# Peripherals.net
KiCad netlist of a schematic drawn in Altium Designer
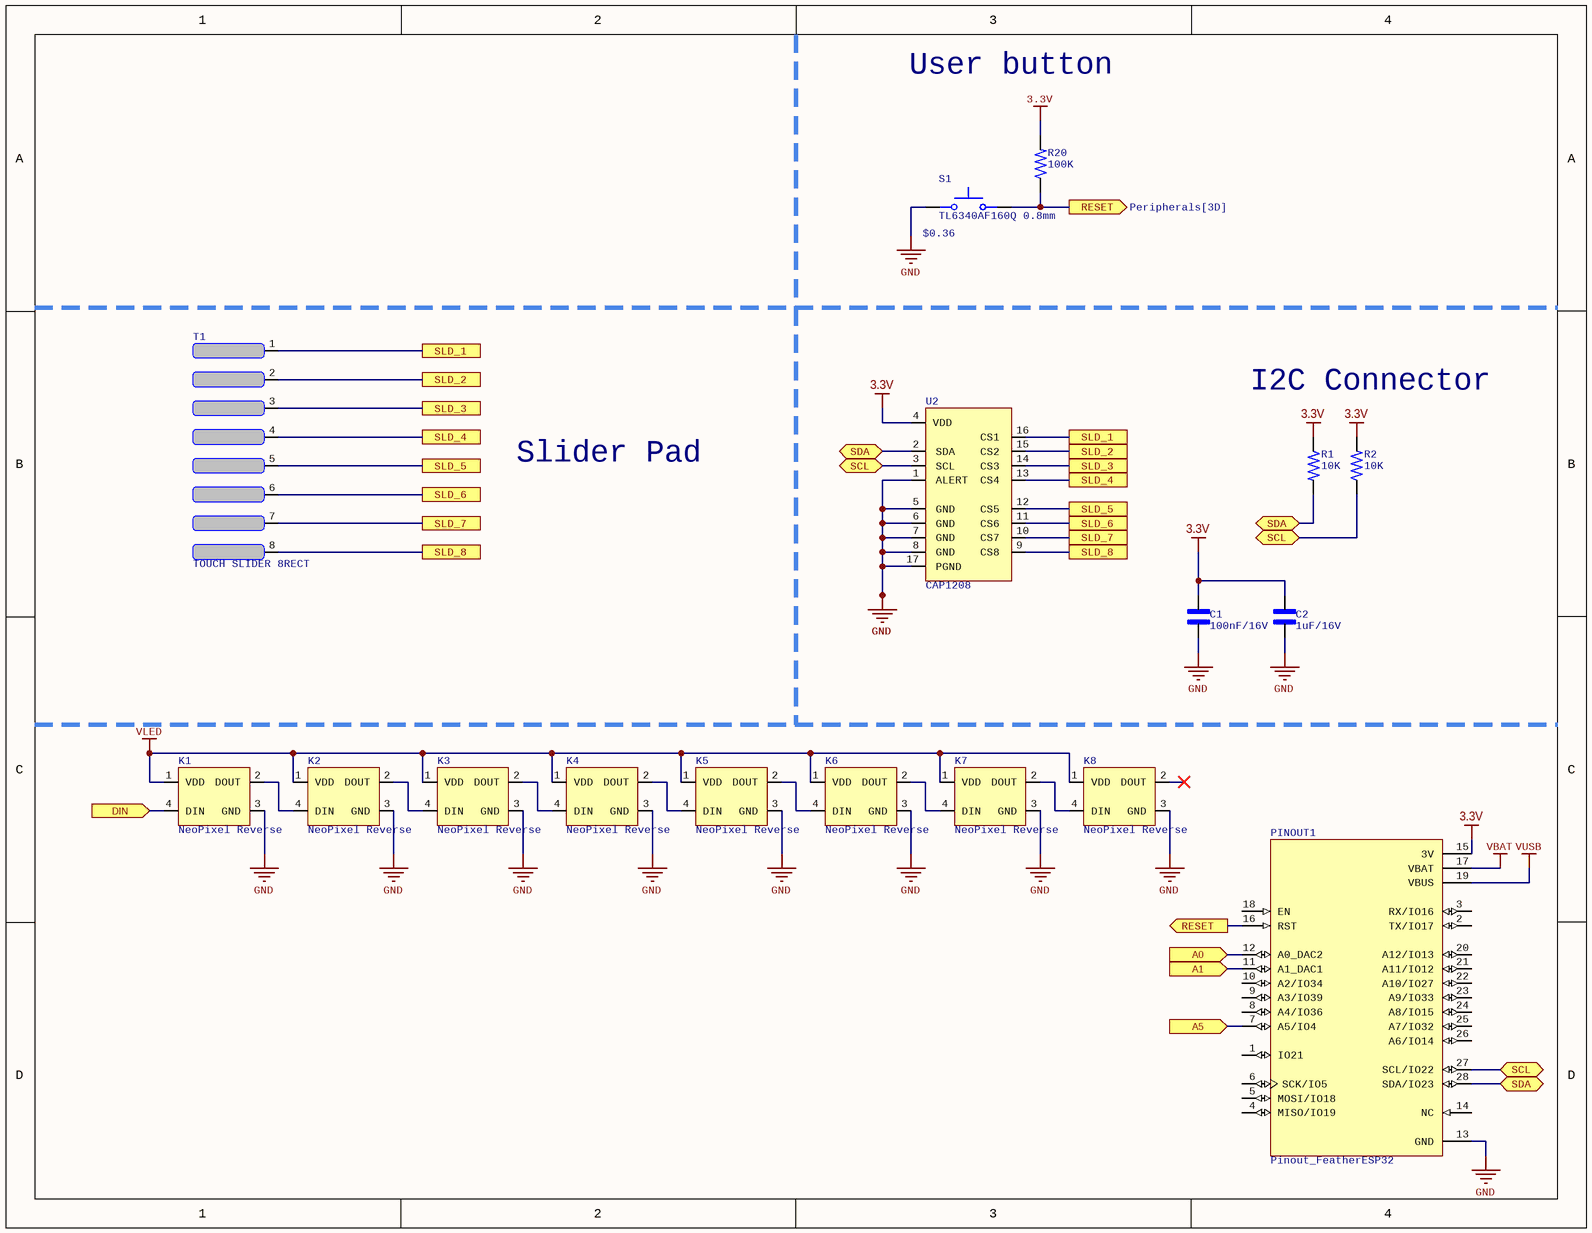
[diagram p0: Peripherals.SchDoc]

(export (version "E")
  (design (tool "Eeschema 10.0.6"))
  (components
    (comp (ref "C1")
      (value "100nF/16V")
      (footprint "C0603")
      (description "MLCC 0603 100nF 16V 10% X5R")
      (fields (field (name "TOLERANCE") "10%"))
      (libsource (lib "Capacitors") (part "C0603 100nF/16V"))
    )
    (comp (ref "C2")
      (value "1uF/16V")
      (footprint "C0603")
      (description "MLCC 0603 1uF 16V 10% X5R")
      (fields (field (name "TOLERANCE") "10%"))
      (libsource (lib "Capacitors") (part "C0603 1uF/16V"))
    )
    (comp (ref "K1")
      (value "NeoPixel Reverse")
      (footprint "SK6812-E")
      (description "NeoPixel Reverse Mount RGB LEDs - SK6812-E")
      (libsource (lib "LED") (part "SK6812-E"))
    )
    (comp (ref "K2")
      (value "NeoPixel Reverse")
      (footprint "SK6812-E")
      (description "NeoPixel Reverse Mount RGB LEDs - SK6812-E")
      (libsource (lib "LED") (part "SK6812-E"))
    )
    (comp (ref "K3")
      (value "NeoPixel Reverse")
      (footprint "SK6812-E")
      (description "NeoPixel Reverse Mount RGB LEDs - SK6812-E")
      (libsource (lib "LED") (part "SK6812-E"))
    )
    (comp (ref "K4")
      (value "NeoPixel Reverse")
      (footprint "SK6812-E")
      (description "NeoPixel Reverse Mount RGB LEDs - SK6812-E")
      (libsource (lib "LED") (part "SK6812-E"))
    )
    (comp (ref "K5")
      (value "NeoPixel Reverse")
      (footprint "SK6812-E")
      (description "NeoPixel Reverse Mount RGB LEDs - SK6812-E")
      (libsource (lib "LED") (part "SK6812-E"))
    )
    (comp (ref "K6")
      (value "NeoPixel Reverse")
      (footprint "SK6812-E")
      (description "NeoPixel Reverse Mount RGB LEDs - SK6812-E")
      (libsource (lib "LED") (part "SK6812-E"))
    )
    (comp (ref "K7")
      (value "NeoPixel Reverse")
      (footprint "SK6812-E")
      (description "NeoPixel Reverse Mount RGB LEDs - SK6812-E")
      (libsource (lib "LED") (part "SK6812-E"))
    )
    (comp (ref "K8")
      (value "NeoPixel Reverse")
      (footprint "SK6812-E")
      (description "NeoPixel Reverse Mount RGB LEDs - SK6812-E")
      (libsource (lib "LED") (part "SK6812-E"))
    )
    (comp (ref "PINOUT1")
      (value "Pinout_FeatherESP32")
      (footprint "SlidersTouch:Pinout_FeatherESP32")
      (description "Breadboard, Prepunched Insulating Non-Plated Through Hole (NPTH) 0.100 (2.54mm)")
      (fields (field (name "MF") "Keystone Electronics") (field (name "MP") "3405"))
      (libsource (lib "SlidersTouch") (part "Pinout_FeatherESP32"))
    )
    (comp (ref "R1")
      (value "10K")
      (footprint "R0603")
      (description "SMD Chip Resistor, 10 kOhm, ± 1%, 100 mW, 0603 [1608 Metric], Thick Film, Anti-Sulfur")
      (fields (field (name "TOLERANCE") "1%"))
      (libsource (lib "Resistors") (part "R0603 10K"))
    )
    (comp (ref "R2")
      (value "10K")
      (footprint "R0603")
      (description "SMD Chip Resistor, 10 kOhm, ± 1%, 100 mW, 0603 [1608 Metric], Thick Film, Anti-Sulfur")
      (fields (field (name "TOLERANCE") "1%"))
      (libsource (lib "Resistors") (part "R0603 10K"))
    )
    (comp (ref "R20")
      (value "100K")
      (footprint "R0603")
      (description "RES 0603 100K OHM 1% 1/10W")
      (fields (field (name "TOLERANCE") "1%"))
      (libsource (lib "Resistors") (part "R0603 100K"))
    )
    (comp (ref "S1")
      (value "TL6340AF160Q 0.8mm")
      (footprint "TL6340AF160Q")
      (fields
        (field (name "MANUFACTURER") "E-Switch")
        (field (name "MANUFACTURER PART NUMBER") "TL6340AF160Q")
        (field (name "PARAMETER 1") "$0.36")
      )
      (libsource (lib "Switches") (part "TL6340AF160Q 0.8mm"))
    )
    (comp (ref "T1")
      (value "TOUCH SLIDER 8RECT")
      (footprint "TOUCH SLIDER 8-RECT KEPOUT")
      (description "8-Segment touch slider")
      (libsource (lib "SlidersTouch") (part "TOUCH SLIDER 8RECT"))
    )
    (comp (ref "U2")
      (value "CAP1208")
      (footprint "QFN16")
      (description "CAP1208 Series 8-Channel Capacitive Touch Surface Mount Proximity - QFN-16")
      (fields
        (field (name "MANUFACTURER") "Microchip")
        (field (name "MANUFACTURER PART NUMBER") "CAP1208-1-A4-TR")
      )
      (libsource (lib "IC Comms") (part "CAP1208"))
    )
  )
  (nets
    (net (code "1") (name "/A0") (class "Default")
      (node (ref "PINOUT1") (pin "12") (pinfunction "A0_DAC2_12") (pintype "bidirectional"))
    )
    (net (code "2") (name "/A1") (class "Default")
      (node (ref "PINOUT1") (pin "11") (pinfunction "A1_DAC1_11") (pintype "bidirectional"))
    )
    (net (code "3") (name "/A5") (class "Default")
      (node (ref "PINOUT1") (pin "7") (pinfunction "A5/IO4_7") (pintype "bidirectional"))
    )
    (net (code "4") (name "/DIN") (class "Default")
      (node (ref "K1") (pin "4") (pinfunction "DIN_4") (pintype "passive"))
    )
    (net (code "5") (name "/RESET") (class "Default")
      (node (ref "PINOUT1") (pin "16") (pinfunction "RST_16") (pintype "input"))
      (node (ref "R20") (pin "1") (pinfunction "1_1") (pintype "passive"))
      (node (ref "S1") (pin "1") (pinfunction "1_1") (pintype "passive"))
    )
    (net (code "6") (name "/SCL") (class "Default")
      (node (ref "PINOUT1") (pin "27") (pinfunction "SCL/IO22_27") (pintype "bidirectional"))
      (node (ref "R2") (pin "1") (pinfunction "1_1") (pintype "passive"))
      (node (ref "U2") (pin "3") (pinfunction "SCL_3") (pintype "passive"))
    )
    (net (code "7") (name "/SDA") (class "Default")
      (node (ref "PINOUT1") (pin "28") (pinfunction "SDA/IO23_28") (pintype "bidirectional"))
      (node (ref "R1") (pin "2") (pinfunction "2_2") (pintype "passive"))
      (node (ref "U2") (pin "2") (pinfunction "SDA_2") (pintype "passive"))
    )
    (net (code "8") (name "/SLD_1") (class "Default")
      (node (ref "T1") (pin "1") (pinfunction "1_1") (pintype "passive"))
      (node (ref "U2") (pin "16") (pinfunction "CS1_16") (pintype "passive"))
    )
    (net (code "9") (name "/SLD_2") (class "Default")
      (node (ref "T1") (pin "2") (pinfunction "2_2") (pintype "passive"))
      (node (ref "U2") (pin "15") (pinfunction "CS2_15") (pintype "passive"))
    )
    (net (code "10") (name "/SLD_3") (class "Default")
      (node (ref "T1") (pin "3") (pinfunction "3_3") (pintype "passive"))
      (node (ref "U2") (pin "14") (pinfunction "CS3_14") (pintype "passive"))
    )
    (net (code "11") (name "/SLD_4") (class "Default")
      (node (ref "T1") (pin "4") (pinfunction "4_4") (pintype "passive"))
      (node (ref "U2") (pin "13") (pinfunction "CS4_13") (pintype "passive"))
    )
    (net (code "12") (name "/SLD_5") (class "Default")
      (node (ref "T1") (pin "5") (pinfunction "5_5") (pintype "passive"))
      (node (ref "U2") (pin "12") (pinfunction "CS5_12") (pintype "passive"))
    )
    (net (code "13") (name "/SLD_6") (class "Default")
      (node (ref "T1") (pin "6") (pinfunction "6_6") (pintype "passive"))
      (node (ref "U2") (pin "11") (pinfunction "CS6_11") (pintype "passive"))
    )
    (net (code "14") (name "/SLD_7") (class "Default")
      (node (ref "T1") (pin "7") (pinfunction "7_7") (pintype "passive"))
      (node (ref "U2") (pin "10") (pinfunction "CS7_10") (pintype "passive"))
    )
    (net (code "15") (name "/SLD_8") (class "Default")
      (node (ref "T1") (pin "8") (pinfunction "8_8") (pintype "passive"))
      (node (ref "U2") (pin "9") (pinfunction "CS8_9") (pintype "passive"))
    )
    (net (code "16") (name "3.3V") (class "Default")
      (node (ref "C1") (pin "1") (pinfunction "1_1") (pintype "passive"))
      (node (ref "C2") (pin "1") (pinfunction "1_1") (pintype "passive"))
      (node (ref "PINOUT1") (pin "15") (pinfunction "3V_15") (pintype "power_in"))
      (node (ref "R1") (pin "1") (pinfunction "1_1") (pintype "passive"))
      (node (ref "R2") (pin "2") (pinfunction "2_2") (pintype "passive"))
      (node (ref "R20") (pin "2") (pinfunction "2_2") (pintype "passive"))
      (node (ref "U2") (pin "4") (pinfunction "VDD_4") (pintype "passive"))
    )
    (net (code "17") (name "GND") (class "Default")
      (node (ref "C1") (pin "2") (pinfunction "2_2") (pintype "passive"))
      (node (ref "C2") (pin "2") (pinfunction "2_2") (pintype "passive"))
      (node (ref "K1") (pin "3") (pinfunction "GND_3") (pintype "passive"))
      (node (ref "K2") (pin "3") (pinfunction "GND_3") (pintype "passive"))
      (node (ref "K3") (pin "3") (pinfunction "GND_3") (pintype "passive"))
      (node (ref "K4") (pin "3") (pinfunction "GND_3") (pintype "passive"))
      (node (ref "K5") (pin "3") (pinfunction "GND_3") (pintype "passive"))
      (node (ref "K6") (pin "3") (pinfunction "GND_3") (pintype "passive"))
      (node (ref "K7") (pin "3") (pinfunction "GND_3") (pintype "passive"))
      (node (ref "K8") (pin "3") (pinfunction "GND_3") (pintype "passive"))
      (node (ref "PINOUT1") (pin "13") (pinfunction "GND_13") (pintype "power_in"))
      (node (ref "S1") (pin "2") (pinfunction "2_2") (pintype "passive"))
      (node (ref "U2") (pin "1") (pinfunction "ALERT_1") (pintype "passive"))
      (node (ref "U2") (pin "17") (pinfunction "PGND_17") (pintype "passive"))
      (node (ref "U2") (pin "5") (pinfunction "GND_5") (pintype "passive"))
      (node (ref "U2") (pin "6") (pinfunction "GND_6") (pintype "passive"))
      (node (ref "U2") (pin "7") (pinfunction "GND_7") (pintype "passive"))
      (node (ref "U2") (pin "8") (pinfunction "GND_8") (pintype "passive"))
    )
    (net (code "18") (name "Net-(K1-DOUT)") (class "Default")
      (node (ref "K1") (pin "2") (pinfunction "DOUT_2") (pintype "passive"))
      (node (ref "K2") (pin "4") (pinfunction "DIN_4") (pintype "passive"))
    )
    (net (code "19") (name "Net-(K2-DOUT)") (class "Default")
      (node (ref "K2") (pin "2") (pinfunction "DOUT_2") (pintype "passive"))
      (node (ref "K3") (pin "4") (pinfunction "DIN_4") (pintype "passive"))
    )
    (net (code "20") (name "Net-(K3-DOUT)") (class "Default")
      (node (ref "K3") (pin "2") (pinfunction "DOUT_2") (pintype "passive"))
      (node (ref "K4") (pin "4") (pinfunction "DIN_4") (pintype "passive"))
    )
    (net (code "21") (name "Net-(K4-DOUT)") (class "Default")
      (node (ref "K4") (pin "2") (pinfunction "DOUT_2") (pintype "passive"))
      (node (ref "K5") (pin "4") (pinfunction "DIN_4") (pintype "passive"))
    )
    (net (code "22") (name "Net-(K5-DOUT)") (class "Default")
      (node (ref "K5") (pin "2") (pinfunction "DOUT_2") (pintype "passive"))
      (node (ref "K6") (pin "4") (pinfunction "DIN_4") (pintype "passive"))
    )
    (net (code "23") (name "Net-(K6-DOUT)") (class "Default")
      (node (ref "K6") (pin "2") (pinfunction "DOUT_2") (pintype "passive"))
      (node (ref "K7") (pin "4") (pinfunction "DIN_4") (pintype "passive"))
    )
    (net (code "24") (name "Net-(K7-DOUT)") (class "Default")
      (node (ref "K7") (pin "2") (pinfunction "DOUT_2") (pintype "passive"))
      (node (ref "K8") (pin "4") (pinfunction "DIN_4") (pintype "passive"))
    )
    (net (code "25") (name "VBAT") (class "Default")
      (node (ref "PINOUT1") (pin "17") (pinfunction "VBAT_17") (pintype "power_in"))
    )
    (net (code "26") (name "VLED") (class "Default")
      (node (ref "K1") (pin "1") (pinfunction "VDD_1") (pintype "passive"))
      (node (ref "K2") (pin "1") (pinfunction "VDD_1") (pintype "passive"))
      (node (ref "K3") (pin "1") (pinfunction "VDD_1") (pintype "passive"))
      (node (ref "K4") (pin "1") (pinfunction "VDD_1") (pintype "passive"))
      (node (ref "K5") (pin "1") (pinfunction "VDD_1") (pintype "passive"))
      (node (ref "K6") (pin "1") (pinfunction "VDD_1") (pintype "passive"))
      (node (ref "K7") (pin "1") (pinfunction "VDD_1") (pintype "passive"))
      (node (ref "K8") (pin "1") (pinfunction "VDD_1") (pintype "passive"))
    )
    (net (code "27") (name "VUSB") (class "Default")
      (node (ref "PINOUT1") (pin "19") (pinfunction "VBUS_19") (pintype "power_in"))
    )
    (net (code "28") (name "unconnected-(K8-DOUT-Pad2)") (class "Default")
      (node (ref "K8") (pin "2") (pinfunction "DOUT_2") (pintype "passive+no_connect"))
    )
    (net (code "29") (name "unconnected-(PINOUT1-A2{slash}IO34-Pad10)") (class "Default")
      (node (ref "PINOUT1") (pin "10") (pinfunction "A2/IO34_10") (pintype "bidirectional"))
    )
    (net (code "30") (name "unconnected-(PINOUT1-A3{slash}IO39-Pad9)") (class "Default")
      (node (ref "PINOUT1") (pin "9") (pinfunction "A3/IO39_9") (pintype "bidirectional"))
    )
    (net (code "31") (name "unconnected-(PINOUT1-A4{slash}IO36-Pad8)") (class "Default")
      (node (ref "PINOUT1") (pin "8") (pinfunction "A4/IO36_8") (pintype "bidirectional"))
    )
    (net (code "32") (name "unconnected-(PINOUT1-A6{slash}IO14-Pad26)") (class "Default")
      (node (ref "PINOUT1") (pin "26") (pinfunction "A6/IO14_26") (pintype "bidirectional"))
    )
    (net (code "33") (name "unconnected-(PINOUT1-A7{slash}IO32-Pad25)") (class "Default")
      (node (ref "PINOUT1") (pin "25") (pinfunction "A7/IO32_25") (pintype "bidirectional"))
    )
    (net (code "34") (name "unconnected-(PINOUT1-A8{slash}IO15-Pad24)") (class "Default")
      (node (ref "PINOUT1") (pin "24") (pinfunction "A8/IO15_24") (pintype "bidirectional"))
    )
    (net (code "35") (name "unconnected-(PINOUT1-A9{slash}IO33-Pad23)") (class "Default")
      (node (ref "PINOUT1") (pin "23") (pinfunction "A9/IO33_23") (pintype "bidirectional"))
    )
    (net (code "36") (name "unconnected-(PINOUT1-A10{slash}IO27-Pad22)") (class "Default")
      (node (ref "PINOUT1") (pin "22") (pinfunction "A10/IO27_22") (pintype "bidirectional"))
    )
    (net (code "37") (name "unconnected-(PINOUT1-A11{slash}IO12-Pad21)") (class "Default")
      (node (ref "PINOUT1") (pin "21") (pinfunction "A11/IO12_21") (pintype "bidirectional"))
    )
    (net (code "38") (name "unconnected-(PINOUT1-A12{slash}IO13-Pad20)") (class "Default")
      (node (ref "PINOUT1") (pin "20") (pinfunction "A12/IO13_20") (pintype "bidirectional"))
    )
    (net (code "39") (name "unconnected-(PINOUT1-EN-Pad18)") (class "Default")
      (node (ref "PINOUT1") (pin "18") (pinfunction "EN_18") (pintype "input"))
    )
    (net (code "40") (name "unconnected-(PINOUT1-IO21-Pad1)") (class "Default")
      (node (ref "PINOUT1") (pin "1") (pinfunction "IO21_1") (pintype "bidirectional"))
    )
    (net (code "41") (name "unconnected-(PINOUT1-MISO{slash}IO19-Pad4)") (class "Default")
      (node (ref "PINOUT1") (pin "4") (pinfunction "MISO/IO19_4") (pintype "bidirectional"))
    )
    (net (code "42") (name "unconnected-(PINOUT1-MOSI{slash}IO18-Pad5)") (class "Default")
      (node (ref "PINOUT1") (pin "5") (pinfunction "MOSI/IO18_5") (pintype "bidirectional"))
    )
    (net (code "43") (name "unconnected-(PINOUT1-NC-Pad14)") (class "Default")
      (node (ref "PINOUT1") (pin "14") (pinfunction "NC_14") (pintype "input"))
    )
    (net (code "44") (name "unconnected-(PINOUT1-RX{slash}IO16-Pad3)") (class "Default")
      (node (ref "PINOUT1") (pin "3") (pinfunction "RX/IO16_3") (pintype "bidirectional"))
    )
    (net (code "45") (name "unconnected-(PINOUT1-SCK{slash}IO5-Pad6)") (class "Default")
      (node (ref "PINOUT1") (pin "6") (pinfunction "SCK/IO5_6") (pintype "bidirectional"))
    )
    (net (code "46") (name "unconnected-(PINOUT1-TX{slash}IO17-Pad2)") (class "Default")
      (node (ref "PINOUT1") (pin "2") (pinfunction "TX/IO17_2") (pintype "bidirectional"))
    )
  )
)
